# PSU3V3-1W-In.net
KiCad netlist of a schematic drawn in Altium Designer
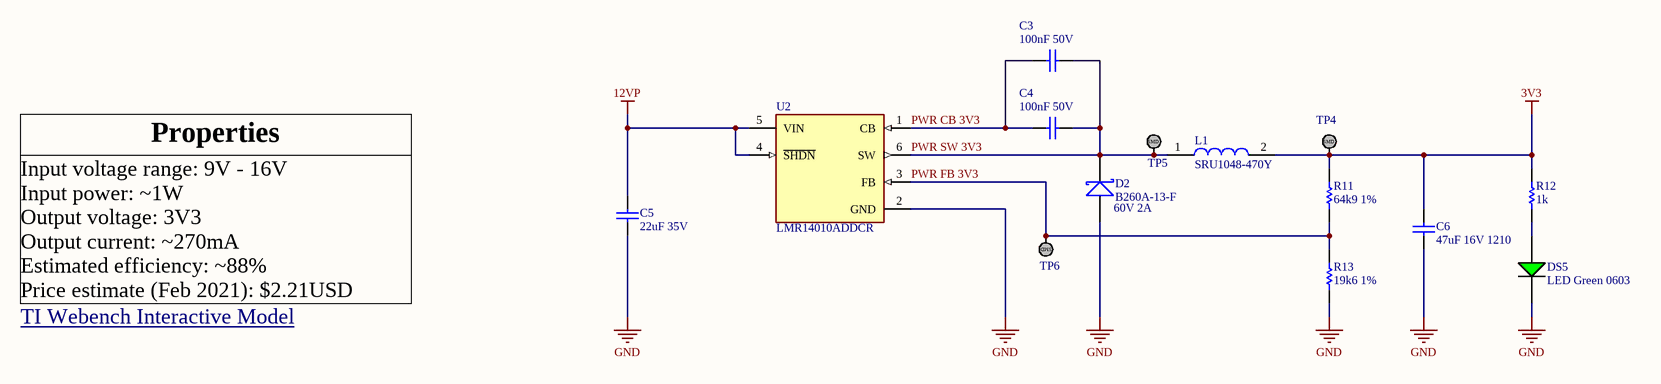
[diagram p0: PSU3V3-1W-In.SchDoc]

(export (version "E")
  (design (tool "Eeschema 10.0.6"))
  (components
    (comp (ref "C3")
      (value "100nF 50V")
      (footprint "Cap_Ceramic_0603")
      (description "Capacitor, Ceramic, SMD, 100nF, 50V, 5%, X7R, 0603")
      (libsource (lib "StandardCapacitors") (part "100nF 50V 5% X7R 0603"))
    )
    (comp (ref "C4")
      (value "100nF 50V")
      (footprint "Cap_Ceramic_0603")
      (description "Capacitor, Ceramic, SMD, 100nF, 50V, 5%, X7R, 0603")
      (libsource (lib "StandardCapacitors") (part "100nF 50V 5% X7R 0603"))
    )
    (comp (ref "C5")
      (value "22uF 35V")
      (footprint "Cap_Ceramic_1206")
      (description "22µF ±20% 35V Ceramic Capacitor X5R 1206 (3216 Metric)")
      (libsource (lib "StandardCapacitors") (part "22uF 35V 20% X5R 1206"))
    )
    (comp (ref "C6")
      (value "47uF 16V 1210")
      (footprint "Cap_Ceramic_1210")
      (description "Capacitor, Ceramic, SMD, 47uF, 16V, 5%, X7R, 1210")
      (libsource (lib "StandardCapacitors") (part "47uF 16V 10% X7R 1210"))
    )
    (comp (ref "D2")
      (value "B260A-13-F")
      (footprint "SMA")
      (description "Diode, Schottky Barrier Rectifier, 60 V, 2 A, B260A-13-F")
      (libsource (lib "QUTMS_DiodeLibrary") (part "B260A-13-F"))
    )
    (comp (ref "DS5")
      (value "LED Green 0603")
      (footprint "LED GREEN 0603")
      (libsource (lib "QUTMS_LEDLibrary") (part "LED Green 0603"))
    )
    (comp (ref "L1")
      (value "SRU1048-470Y")
      (footprint "SRU1048")
      (description "Fixed Inductors 47uH 30% SMD 1048")
      (libsource (lib "QUTMS_InductorLibrary") (part "SRU1048-470Y"))
    )
    (comp (ref "R11")
      (value "64k9 1%")
      (footprint "Res_ThinFilm_0603")
      (description "Resistor, SMD, 64k9, 0.1W, 5%, 0603")
      (libsource (lib "StandardResistors") (part "64k9 1% 0603"))
    )
    (comp (ref "R12")
      (value "1k")
      (footprint "Res_ThinFilm_0603")
      (description "Resistor, SMD, 1k, 0.1W, 5%, 0603")
      (libsource (lib "StandardResistors") (part "1k 5% 0603"))
    )
    (comp (ref "R13")
      (value "19k6 1%")
      (footprint "Res_ThinFilm_0603")
      (description "Resistor, SMD, 19k6, 0.1W, 5%, 0603")
      (libsource (lib "StandardResistors") (part "19k6 1% 0603"))
    )
    (comp (ref "TP4")
      (value "TestPoint_SMD")
      (footprint "TestPointSMD")
      (libsource (lib "StandardTest") (part "TestPoint_SMD"))
    )
    (comp (ref "TP5")
      (value "TestPoint_SMD")
      (footprint "TestPointSMD")
      (libsource (lib "StandardTest") (part "TestPoint_SMD"))
    )
    (comp (ref "TP6")
      (value "TestPoint_SMD")
      (footprint "TestPointSMD")
      (libsource (lib "StandardTest") (part "TestPoint_SMD"))
    )
    (comp (ref "U2")
      (value "LMR14010ADDCR")
      (footprint "FP-DDC0006A-MFG")
      (description "IC REG BUCK ADJ 1A TSOT23-6")
      (fields
        (field (name "MANUFACTURER") "Texas Instruments")
        (field (name "OCTOPART") "https://octopart.com/lmr14010addcr-texas+instruments-90753290")
      )
      (libsource (lib "Altium Content Vault") (part "248534993f007311ab4e1890f26e637"))
    )
  )
  (nets
    (net (code "1") (name "/PWR CB 3V3") (class "Default")
      (node (ref "C3") (pin "1") (pinfunction "1_1") (pintype "passive"))
      (node (ref "C4") (pin "1") (pinfunction "1_1") (pintype "passive"))
      (node (ref "U2") (pin "1") (pinfunction "CB_1") (pintype "input"))
    )
    (net (code "2") (name "/PWR FB 3V3") (class "Default")
      (node (ref "R11") (pin "1") (pinfunction "1_1") (pintype "passive"))
      (node (ref "R13") (pin "2") (pinfunction "2_2") (pintype "passive"))
      (node (ref "TP6") (pin "1") (pinfunction "1_1") (pintype "passive"))
      (node (ref "U2") (pin "3") (pinfunction "FB_3") (pintype "input"))
    )
    (net (code "3") (name "/PWR SW 3V3") (class "Default")
      (node (ref "C3") (pin "2") (pinfunction "2_2") (pintype "passive"))
      (node (ref "C4") (pin "2") (pinfunction "2_2") (pintype "passive"))
      (node (ref "D2") (pin "K") (pinfunction "K_K") (pintype "passive"))
      (node (ref "L1") (pin "1") (pinfunction "1_1") (pintype "passive"))
      (node (ref "TP5") (pin "1") (pinfunction "1_1") (pintype "passive"))
      (node (ref "U2") (pin "6") (pinfunction "SW_6") (pintype "output"))
    )
    (net (code "4") (name "3V3") (class "Default")
      (node (ref "C6") (pin "2") (pinfunction "2_2") (pintype "passive"))
      (node (ref "L1") (pin "2") (pinfunction "2_2") (pintype "passive"))
      (node (ref "R11") (pin "2") (pinfunction "2_2") (pintype "passive"))
      (node (ref "R12") (pin "2") (pinfunction "2_2") (pintype "passive"))
      (node (ref "TP4") (pin "1") (pinfunction "1_1") (pintype "passive"))
    )
    (net (code "5") (name "12VP") (class "Default")
      (node (ref "C5") (pin "1") (pinfunction "1_1") (pintype "passive"))
      (node (ref "U2") (pin "4") (pinfunction "~{SHDN}_4") (pintype "input"))
      (node (ref "U2") (pin "5") (pinfunction "VIN_5") (pintype "power_in"))
    )
    (net (code "6") (name "GND") (class "Default")
      (node (ref "C5") (pin "2") (pinfunction "2_2") (pintype "passive"))
      (node (ref "C6") (pin "1") (pinfunction "1_1") (pintype "passive"))
      (node (ref "D2") (pin "A") (pinfunction "A_A") (pintype "passive"))
      (node (ref "DS5") (pin "2") (pinfunction "C_2") (pintype "passive"))
      (node (ref "R13") (pin "1") (pinfunction "1_1") (pintype "passive"))
      (node (ref "U2") (pin "2") (pinfunction "GND_2") (pintype "power_in"))
    )
    (net (code "7") (name "Net-(DS5-A)") (class "Default")
      (node (ref "DS5") (pin "1") (pinfunction "A_1") (pintype "passive"))
      (node (ref "R12") (pin "1") (pinfunction "1_1") (pintype "passive"))
    )
  )
)
